# connector.net
KiCad netlist of a schematic drawn in EAGLE
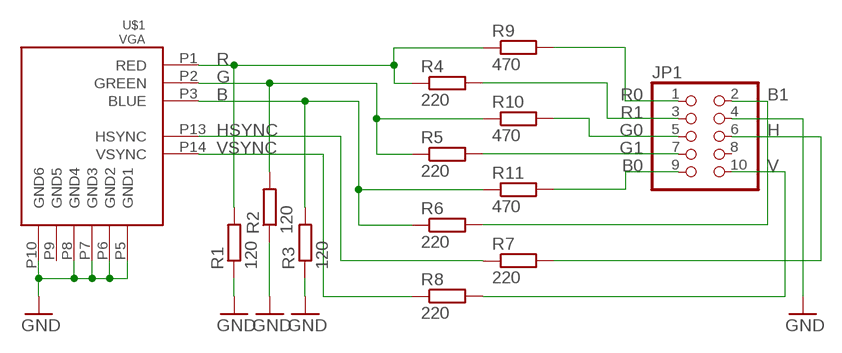
[diagram p0: schematic, sheet 1]

(export (version "E")
  (design (tool "Eeschema 10.0.6"))
  (components
    (comp (ref "JP1")
      (value "PINHD-2X5")
      (footprint "eagle-import:2X05")
      (libsource (lib "eagle-import") (part "PINHD-2X5"))
    )
    (comp (ref "R1")
      (value "120")
      (footprint "eagle-import:0204_7")
      (libsource (lib "eagle-import") (part "R-EU_0204/7"))
    )
    (comp (ref "R2")
      (value "120")
      (footprint "eagle-import:0204_7")
      (libsource (lib "eagle-import") (part "R-EU_0204/7"))
    )
    (comp (ref "R3")
      (value "120")
      (footprint "eagle-import:0204_7")
      (libsource (lib "eagle-import") (part "R-EU_0204/7"))
    )
    (comp (ref "R4")
      (value "220")
      (footprint "eagle-import:0204_7")
      (libsource (lib "eagle-import") (part "R-EU_0204/7"))
    )
    (comp (ref "R5")
      (value "220")
      (footprint "eagle-import:0204_7")
      (libsource (lib "eagle-import") (part "R-EU_0204/7"))
    )
    (comp (ref "R6")
      (value "220")
      (footprint "eagle-import:0204_7")
      (libsource (lib "eagle-import") (part "R-EU_0204/7"))
    )
    (comp (ref "R7")
      (value "220")
      (footprint "eagle-import:0204_7")
      (libsource (lib "eagle-import") (part "R-EU_0204/7"))
    )
    (comp (ref "R8")
      (value "220")
      (footprint "eagle-import:0204_7")
      (libsource (lib "eagle-import") (part "R-EU_0204/7"))
    )
    (comp (ref "R9")
      (value "470")
      (footprint "eagle-import:0204_7")
      (libsource (lib "eagle-import") (part "R-EU_0204/7"))
    )
    (comp (ref "R10")
      (value "470")
      (footprint "eagle-import:0204_7")
      (libsource (lib "eagle-import") (part "R-EU_0204/7"))
    )
    (comp (ref "R11")
      (value "470")
      (footprint "eagle-import:0204_7")
      (libsource (lib "eagle-import") (part "R-EU_0204/7"))
    )
    (comp (ref "U$1")
      (value "VGA")
      (footprint "eagle-import:FCI_DSUB_HD_15_RA")
      (libsource (lib "eagle-import") (part "VGA"))
    )
  )
  (nets
    (net (code "1") (name "/B") (class "Default")
      (node (ref "R11") (pin "1") (pinfunction "1_1") (pintype "passive"))
      (node (ref "R3") (pin "2") (pinfunction "2_2") (pintype "passive"))
      (node (ref "R6") (pin "1") (pinfunction "1_1") (pintype "passive"))
      (node (ref "U$1") (pin "P3") (pinfunction "BLUE_P3") (pintype "bidirectional"))
    )
    (net (code "2") (name "/B0") (class "Default")
      (node (ref "JP1") (pin "9") (pinfunction "9_9") (pintype "passive"))
      (node (ref "R11") (pin "2") (pinfunction "2_2") (pintype "passive"))
    )
    (net (code "3") (name "/B1") (class "Default")
      (node (ref "JP1") (pin "2") (pinfunction "2_2") (pintype "passive"))
      (node (ref "R6") (pin "2") (pinfunction "2_2") (pintype "passive"))
    )
    (net (code "4") (name "/G") (class "Default")
      (node (ref "R10") (pin "1") (pinfunction "1_1") (pintype "passive"))
      (node (ref "R2") (pin "2") (pinfunction "2_2") (pintype "passive"))
      (node (ref "R5") (pin "1") (pinfunction "1_1") (pintype "passive"))
      (node (ref "U$1") (pin "P2") (pinfunction "GREEN_P2") (pintype "bidirectional"))
    )
    (net (code "5") (name "/G0") (class "Default")
      (node (ref "JP1") (pin "5") (pinfunction "5_5") (pintype "passive"))
      (node (ref "R10") (pin "2") (pinfunction "2_2") (pintype "passive"))
    )
    (net (code "6") (name "/G1") (class "Default")
      (node (ref "JP1") (pin "7") (pinfunction "7_7") (pintype "passive"))
      (node (ref "R5") (pin "2") (pinfunction "2_2") (pintype "passive"))
    )
    (net (code "7") (name "/H") (class "Default")
      (node (ref "JP1") (pin "6") (pinfunction "6_6") (pintype "passive"))
      (node (ref "R7") (pin "2") (pinfunction "2_2") (pintype "passive"))
    )
    (net (code "8") (name "/HSYNC") (class "Default")
      (node (ref "R7") (pin "1") (pinfunction "1_1") (pintype "passive"))
      (node (ref "U$1") (pin "P13") (pinfunction "HSYNC_P13") (pintype "bidirectional"))
    )
    (net (code "9") (name "/R") (class "Default")
      (node (ref "R1") (pin "2") (pinfunction "2_2") (pintype "passive"))
      (node (ref "R4") (pin "1") (pinfunction "1_1") (pintype "passive"))
      (node (ref "R9") (pin "1") (pinfunction "1_1") (pintype "passive"))
      (node (ref "U$1") (pin "P1") (pinfunction "RED_P1") (pintype "bidirectional"))
    )
    (net (code "10") (name "/R0") (class "Default")
      (node (ref "JP1") (pin "1") (pinfunction "1_1") (pintype "passive"))
      (node (ref "R9") (pin "2") (pinfunction "2_2") (pintype "passive"))
    )
    (net (code "11") (name "/R1") (class "Default")
      (node (ref "JP1") (pin "3") (pinfunction "3_3") (pintype "passive"))
      (node (ref "R4") (pin "2") (pinfunction "2_2") (pintype "passive"))
    )
    (net (code "12") (name "/V") (class "Default")
      (node (ref "JP1") (pin "10") (pinfunction "10_10") (pintype "passive"))
      (node (ref "R8") (pin "2") (pinfunction "2_2") (pintype "passive"))
    )
    (net (code "13") (name "/VSYNC") (class "Default")
      (node (ref "R8") (pin "1") (pinfunction "1_1") (pintype "passive"))
      (node (ref "U$1") (pin "P14") (pinfunction "VSYNC_P14") (pintype "bidirectional"))
    )
    (net (code "14") (name "GND") (class "Default")
      (node (ref "JP1") (pin "4") (pinfunction "4_4") (pintype "passive"))
      (node (ref "R1") (pin "1") (pinfunction "1_1") (pintype "passive"))
      (node (ref "R2") (pin "1") (pinfunction "1_1") (pintype "passive"))
      (node (ref "R3") (pin "1") (pinfunction "1_1") (pintype "passive"))
      (node (ref "U$1") (pin "P10") (pinfunction "GND6_P10") (pintype "bidirectional"))
      (node (ref "U$1") (pin "P5") (pinfunction "GND1_P5") (pintype "bidirectional"))
      (node (ref "U$1") (pin "P6") (pinfunction "GND2_P6") (pintype "bidirectional"))
      (node (ref "U$1") (pin "P7") (pinfunction "GND3_P7") (pintype "bidirectional"))
      (node (ref "U$1") (pin "P8") (pinfunction "GND4_P8") (pintype "bidirectional"))
    )
    (net (code "15") (name "unconnected-(JP1-Pad8)") (class "Default")
      (node (ref "JP1") (pin "8") (pinfunction "8_8") (pintype "passive"))
    )
    (net (code "16") (name "unconnected-(U$1-GND5-PadP9)") (class "Default")
      (node (ref "U$1") (pin "P9") (pinfunction "GND5_P9") (pintype "bidirectional"))
    )
  )
)
